# Remote.net
KiCad netlist of a schematic drawn in Altium Designer
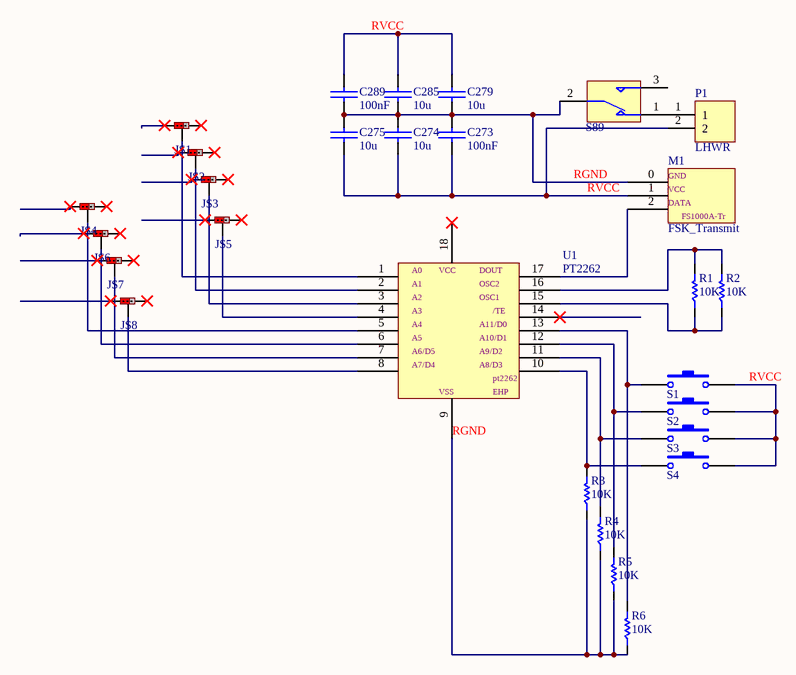
[diagram p0: Remote.SchDoc]

(export (version "E")
  (design (tool "Eeschema 10.0.6"))
  (components
    (comp (ref "C273")
      (value "100nF")
      (footprint "SMD_CAP_1206")
      (description "Bipolar Capacitor")
      (fields (field (name "VOLTAGE") "100V") (field (name "DESIGNER") "Saeid Jorablo"))
      (libsource (lib "My Library") (part "Cap-Bipolar"))
    )
    (comp (ref "C274")
      (value "10u")
      (footprint "SMD_CAP_1206")
      (description "Bipolar Capacitor")
      (fields (field (name "VOLTAGE") "100V") (field (name "DESIGNER") "Saeid Jorablo"))
      (libsource (lib "My Library") (part "Cap-Bipolar"))
    )
    (comp (ref "C275")
      (value "10u")
      (footprint "SMD_CAP_1206")
      (description "Bipolar Capacitor")
      (fields (field (name "VOLTAGE") "100V") (field (name "DESIGNER") "Saeid Jorablo"))
      (libsource (lib "My Library") (part "Cap-Bipolar"))
    )
    (comp (ref "C279")
      (value "10u")
      (footprint "SMD_CAP_1206")
      (description "Bipolar Capacitor")
      (fields (field (name "VOLTAGE") "100V") (field (name "DESIGNER") "Saeid Jorablo"))
      (libsource (lib "My Library") (part "Cap-Bipolar"))
    )
    (comp (ref "C285")
      (value "10u")
      (footprint "SMD_CAP_1206")
      (description "Bipolar Capacitor")
      (fields (field (name "VOLTAGE") "100V") (field (name "DESIGNER") "Saeid Jorablo"))
      (libsource (lib "My Library") (part "Cap-Bipolar"))
    )
    (comp (ref "C289")
      (value "100nF")
      (footprint "SMD_CAP_1206")
      (description "Bipolar Capacitor")
      (fields (field (name "VOLTAGE") "100V") (field (name "DESIGNER") "Saeid Jorablo"))
      (libsource (lib "My Library") (part "Cap-Bipolar"))
    )
    (comp (ref "JS1")
      (value "JumperSMD 3Pin")
      (footprint "JumperSMD 3Pin")
      (libsource (lib "R2T Team Library") (part "JumperSMD 3Pin"))
    )
    (comp (ref "JS2")
      (value "JumperSMD 3Pin")
      (footprint "JumperSMD 3Pin")
      (libsource (lib "R2T Team Library") (part "JumperSMD 3Pin"))
    )
    (comp (ref "JS3")
      (value "JumperSMD 3Pin")
      (footprint "JumperSMD 3Pin")
      (libsource (lib "R2T Team Library") (part "JumperSMD 3Pin"))
    )
    (comp (ref "JS4")
      (value "JumperSMD 3Pin")
      (footprint "JumperSMD 3Pin")
      (libsource (lib "R2T Team Library") (part "JumperSMD 3Pin"))
    )
    (comp (ref "JS5")
      (value "JumperSMD 3Pin")
      (footprint "JumperSMD 3Pin")
      (libsource (lib "R2T Team Library") (part "JumperSMD 3Pin"))
    )
    (comp (ref "JS6")
      (value "JumperSMD 3Pin")
      (footprint "JumperSMD 3Pin")
      (libsource (lib "R2T Team Library") (part "JumperSMD 3Pin"))
    )
    (comp (ref "JS7")
      (value "JumperSMD 3Pin")
      (footprint "JumperSMD 3Pin")
      (libsource (lib "R2T Team Library") (part "JumperSMD 3Pin"))
    )
    (comp (ref "JS8")
      (value "JumperSMD 3Pin")
      (footprint "JumperSMD 3Pin")
      (libsource (lib "R2T Team Library") (part "JumperSMD 3Pin"))
    )
    (comp (ref "M1")
      (value "FSK_Transmit")
      (footprint "FSK_TRA")
      (libsource (lib "Soga Library") (part "FSK_Transmit"))
    )
    (comp (ref "P1")
      (value "LHWR")
      (footprint "Polarized Header 2")
      (fields (field (name "DESIGNER:") "Hamed Jafarzadeh - www.R2T.ir"))
      (libsource (lib "R2T Team Library") (part "2pin LHWR"))
    )
    (comp (ref "R1")
      (value "10K")
      (footprint "RES 1206 (3216X08L)")
      (description "Resistor")
      (fields (field (name "TOLERANCE") "5%") (field (name "POWER") "1/8 W"))
      (libsource (lib "My Library") (part "Resistor"))
    )
    (comp (ref "R2")
      (value "10K")
      (footprint "RES 1206 (3216X08L)")
      (description "Resistor")
      (fields (field (name "TOLERANCE") "5%") (field (name "POWER") "1/8 W"))
      (libsource (lib "My Library") (part "Resistor"))
    )
    (comp (ref "R3")
      (value "10K")
      (footprint "RES 1206 (3216X08L)")
      (description "Resistor")
      (fields (field (name "TOLERANCE") "5%") (field (name "POWER") "1/8 W"))
      (libsource (lib "My Library") (part "Resistor"))
    )
    (comp (ref "R4")
      (value "10K")
      (footprint "RES 1206 (3216X08L)")
      (description "Resistor")
      (fields (field (name "TOLERANCE") "5%") (field (name "POWER") "1/8 W"))
      (libsource (lib "My Library") (part "Resistor"))
    )
    (comp (ref "R5")
      (value "10K")
      (footprint "RES 1206 (3216X08L)")
      (description "Resistor")
      (fields (field (name "TOLERANCE") "5%") (field (name "POWER") "1/8 W"))
      (libsource (lib "My Library") (part "Resistor"))
    )
    (comp (ref "R6")
      (value "10K")
      (footprint "RES 1206 (3216X08L)")
      (description "Resistor")
      (fields (field (name "TOLERANCE") "5%") (field (name "POWER") "1/8 W"))
      (libsource (lib "My Library") (part "Resistor"))
    )
    (comp (ref "S1")
      (value "Switch PB")
      (footprint "Switch - Push to On")
      (description "Push Button Switch")
      (libsource (lib "My Library") (part "Switch PB"))
    )
    (comp (ref "S2")
      (value "Switch PB")
      (footprint "Switch - Push to On")
      (description "Push Button Switch")
      (libsource (lib "My Library") (part "Switch PB"))
    )
    (comp (ref "S3")
      (value "Switch PB")
      (footprint "Switch - Push to On")
      (description "Push Button Switch")
      (libsource (lib "My Library") (part "Switch PB"))
    )
    (comp (ref "S4")
      (value "Switch PB")
      (footprint "Switch - Push to On")
      (description "Push Button Switch")
      (libsource (lib "My Library") (part "Switch PB"))
    )
    (comp (ref "S89")
      (value "Switch SPDT_Subminiator")
      (footprint "SPDT Subminiator")
      (description "Subminiator SPDT Switch")
      (libsource (lib "My Library") (part "Switch SPDT_Subminiator"))
    )
    (comp (ref "U1") (value "PT2262") (footprint "PT2262") (libsource (lib "Soga Library") (part "PT2262")))
  )
  (nets
    (net (code "1") (name "/RGND") (class "Default")
      (node (ref "C273") (pin "1") (pinfunction "+_1") (pintype "passive"))
      (node (ref "C274") (pin "1") (pinfunction "+_1") (pintype "passive"))
      (node (ref "C275") (pin "1") (pinfunction "+_1") (pintype "passive"))
      (node (ref "C279") (pin "1") (pinfunction "+_1") (pintype "passive"))
      (node (ref "C285") (pin "1") (pinfunction "+_1") (pintype "passive"))
      (node (ref "C289") (pin "1") (pinfunction "+_1") (pintype "passive"))
      (node (ref "M1") (pin "0") (pinfunction "0_0") (pintype "passive"))
      (node (ref "R3") (pin "1") (pinfunction "1_1") (pintype "passive"))
      (node (ref "R4") (pin "1") (pinfunction "1_1") (pintype "passive"))
      (node (ref "R5") (pin "1") (pinfunction "1_1") (pintype "passive"))
      (node (ref "R6") (pin "1") (pinfunction "1_1") (pintype "passive"))
      (node (ref "S89") (pin "2") (pinfunction "2_2") (pintype "passive"))
      (node (ref "U1") (pin "9") (pinfunction "9_9") (pintype "passive"))
    )
    (net (code "2") (name "/RVCC") (class "Default")
      (node (ref "C273") (pin "2") (pinfunction "-_2") (pintype "passive"))
      (node (ref "C274") (pin "2") (pinfunction "-_2") (pintype "passive"))
      (node (ref "C275") (pin "2") (pinfunction "-_2") (pintype "passive"))
      (node (ref "C279") (pin "2") (pinfunction "-_2") (pintype "passive"))
      (node (ref "C285") (pin "2") (pinfunction "-_2") (pintype "passive"))
      (node (ref "C289") (pin "2") (pinfunction "-_2") (pintype "passive"))
      (node (ref "M1") (pin "1") (pinfunction "1_1") (pintype "passive"))
      (node (ref "P1") (pin "2") (pinfunction "2_2") (pintype "passive"))
      (node (ref "S1") (pin "2") (pinfunction "2_2") (pintype "passive"))
      (node (ref "S2") (pin "2") (pinfunction "2_2") (pintype "passive"))
      (node (ref "S3") (pin "2") (pinfunction "2_2") (pintype "passive"))
      (node (ref "S4") (pin "2") (pinfunction "2_2") (pintype "passive"))
    )
    (net (code "3") (name "Net-(JS1-Pad2)") (class "Default")
      (node (ref "JS1") (pin "2") (pintype "passive"))
      (node (ref "U1") (pin "1") (pinfunction "1_1") (pintype "passive"))
    )
    (net (code "4") (name "Net-(JS2-Pad2)") (class "Default")
      (node (ref "JS2") (pin "2") (pintype "passive"))
      (node (ref "U1") (pin "2") (pinfunction "2_2") (pintype "passive"))
    )
    (net (code "5") (name "Net-(JS3-Pad2)") (class "Default")
      (node (ref "JS3") (pin "2") (pintype "passive"))
      (node (ref "U1") (pin "3") (pinfunction "3_3") (pintype "passive"))
    )
    (net (code "6") (name "Net-(JS4-Pad2)") (class "Default")
      (node (ref "JS4") (pin "2") (pintype "passive"))
      (node (ref "U1") (pin "5") (pinfunction "5_5") (pintype "passive"))
    )
    (net (code "7") (name "Net-(JS5-Pad2)") (class "Default")
      (node (ref "JS5") (pin "2") (pintype "passive"))
      (node (ref "U1") (pin "4") (pinfunction "4_4") (pintype "passive"))
    )
    (net (code "8") (name "Net-(JS6-Pad2)") (class "Default")
      (node (ref "JS6") (pin "2") (pintype "passive"))
      (node (ref "U1") (pin "6") (pinfunction "6_6") (pintype "passive"))
    )
    (net (code "9") (name "Net-(JS7-Pad2)") (class "Default")
      (node (ref "JS7") (pin "2") (pintype "passive"))
      (node (ref "U1") (pin "7") (pinfunction "7_7") (pintype "passive"))
    )
    (net (code "10") (name "Net-(JS8-Pad2)") (class "Default")
      (node (ref "JS8") (pin "2") (pintype "passive"))
      (node (ref "U1") (pin "8") (pinfunction "8_8") (pintype "passive"))
    )
    (net (code "11") (name "Net-(M1-Pad2)") (class "Default")
      (node (ref "M1") (pin "2") (pinfunction "2_2") (pintype "passive"))
      (node (ref "U1") (pin "17") (pinfunction "17_17") (pintype "passive"))
    )
    (net (code "12") (name "Net-(P1-Pad1)") (class "Default")
      (node (ref "P1") (pin "1") (pinfunction "1_1") (pintype "passive"))
      (node (ref "S89") (pin "1") (pinfunction "1_1") (pintype "passive"))
    )
    (net (code "13") (name "Net-(R1-Pad1)") (class "Default")
      (node (ref "R1") (pin "1") (pinfunction "1_1") (pintype "passive"))
      (node (ref "R2") (pin "1") (pinfunction "1_1") (pintype "passive"))
      (node (ref "U1") (pin "15") (pinfunction "15_15") (pintype "passive"))
    )
    (net (code "14") (name "Net-(R1-Pad2)") (class "Default")
      (node (ref "R1") (pin "2") (pinfunction "2_2") (pintype "passive"))
      (node (ref "R2") (pin "2") (pinfunction "2_2") (pintype "passive"))
      (node (ref "U1") (pin "16") (pinfunction "16_16") (pintype "passive"))
    )
    (net (code "15") (name "Net-(R3-Pad2)") (class "Default")
      (node (ref "R3") (pin "2") (pinfunction "2_2") (pintype "passive"))
      (node (ref "S4") (pin "1") (pinfunction "1_1") (pintype "passive"))
      (node (ref "U1") (pin "10") (pinfunction "10_10") (pintype "passive"))
    )
    (net (code "16") (name "Net-(R4-Pad2)") (class "Default")
      (node (ref "R4") (pin "2") (pinfunction "2_2") (pintype "passive"))
      (node (ref "S3") (pin "1") (pinfunction "1_1") (pintype "passive"))
      (node (ref "U1") (pin "11") (pinfunction "11_11") (pintype "passive"))
    )
    (net (code "17") (name "Net-(R5-Pad2)") (class "Default")
      (node (ref "R5") (pin "2") (pinfunction "2_2") (pintype "passive"))
      (node (ref "S2") (pin "1") (pinfunction "1_1") (pintype "passive"))
      (node (ref "U1") (pin "12") (pinfunction "12_12") (pintype "passive"))
    )
    (net (code "18") (name "Net-(R6-Pad2)") (class "Default")
      (node (ref "R6") (pin "2") (pinfunction "2_2") (pintype "passive"))
      (node (ref "S1") (pin "1") (pinfunction "1_1") (pintype "passive"))
      (node (ref "U1") (pin "13") (pinfunction "13_13") (pintype "passive"))
    )
    (net (code "19") (name "unconnected-(JS1-Pad1)") (class "Default")
      (node (ref "JS1") (pin "1") (pintype "passive+no_connect"))
    )
    (net (code "20") (name "unconnected-(JS1-Pad3)") (class "Default")
      (node (ref "JS1") (pin "3") (pintype "passive+no_connect"))
    )
    (net (code "21") (name "unconnected-(JS2-Pad1)") (class "Default")
      (node (ref "JS2") (pin "1") (pintype "passive+no_connect"))
    )
    (net (code "22") (name "unconnected-(JS2-Pad3)") (class "Default")
      (node (ref "JS2") (pin "3") (pintype "passive+no_connect"))
    )
    (net (code "23") (name "unconnected-(JS3-Pad1)") (class "Default")
      (node (ref "JS3") (pin "1") (pintype "passive+no_connect"))
    )
    (net (code "24") (name "unconnected-(JS3-Pad3)") (class "Default")
      (node (ref "JS3") (pin "3") (pintype "passive+no_connect"))
    )
    (net (code "25") (name "unconnected-(JS4-Pad1)") (class "Default")
      (node (ref "JS4") (pin "1") (pintype "passive+no_connect"))
    )
    (net (code "26") (name "unconnected-(JS4-Pad3)") (class "Default")
      (node (ref "JS4") (pin "3") (pintype "passive+no_connect"))
    )
    (net (code "27") (name "unconnected-(JS5-Pad1)") (class "Default")
      (node (ref "JS5") (pin "1") (pintype "passive+no_connect"))
    )
    (net (code "28") (name "unconnected-(JS5-Pad3)") (class "Default")
      (node (ref "JS5") (pin "3") (pintype "passive+no_connect"))
    )
    (net (code "29") (name "unconnected-(JS6-Pad1)") (class "Default")
      (node (ref "JS6") (pin "1") (pintype "passive+no_connect"))
    )
    (net (code "30") (name "unconnected-(JS6-Pad3)") (class "Default")
      (node (ref "JS6") (pin "3") (pintype "passive+no_connect"))
    )
    (net (code "31") (name "unconnected-(JS7-Pad1)") (class "Default")
      (node (ref "JS7") (pin "1") (pintype "passive+no_connect"))
    )
    (net (code "32") (name "unconnected-(JS7-Pad3)") (class "Default")
      (node (ref "JS7") (pin "3") (pintype "passive+no_connect"))
    )
    (net (code "33") (name "unconnected-(JS8-Pad1)") (class "Default")
      (node (ref "JS8") (pin "1") (pintype "passive+no_connect"))
    )
    (net (code "34") (name "unconnected-(JS8-Pad3)") (class "Default")
      (node (ref "JS8") (pin "3") (pintype "passive+no_connect"))
    )
    (net (code "35") (name "unconnected-(S89-Pad3)") (class "Default")
      (node (ref "S89") (pin "3") (pinfunction "3_3") (pintype "passive"))
    )
    (net (code "36") (name "unconnected-(U1-Pad14)") (class "Default")
      (node (ref "U1") (pin "14") (pinfunction "14_14") (pintype "passive+no_connect"))
    )
    (net (code "37") (name "unconnected-(U1-Pad18)") (class "Default")
      (node (ref "U1") (pin "18") (pinfunction "18_18") (pintype "passive+no_connect"))
    )
  )
)
